# SiPM_Array_v3_2.net
KiCad netlist of a schematic drawn in Altium Designer
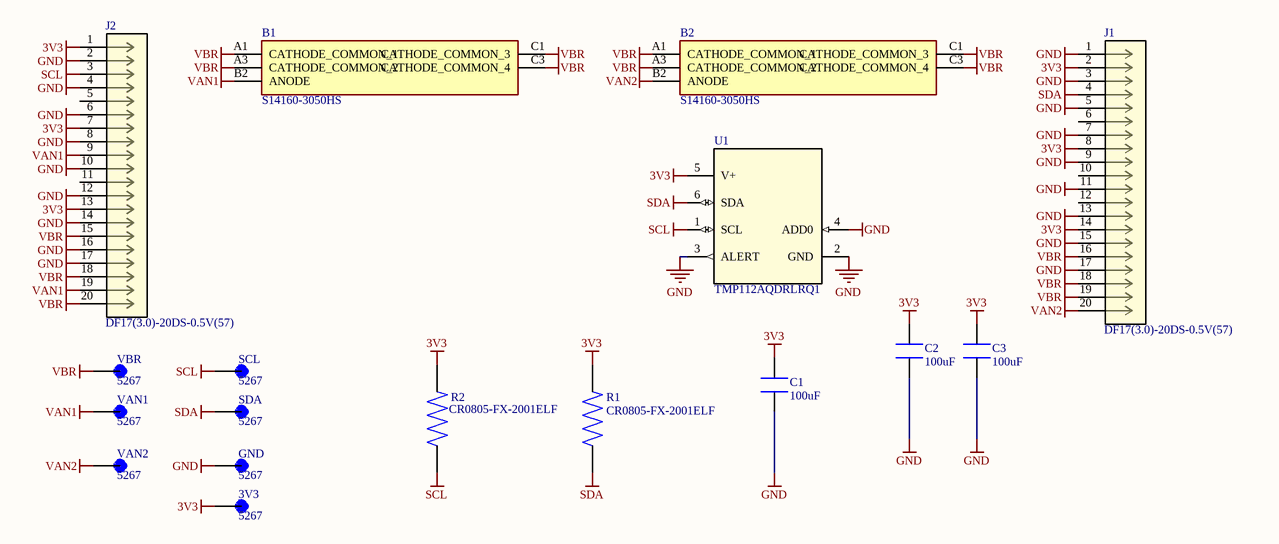
[diagram p0: SiPM_Array_v3.2.SchDoc]

(export (version "E")
  (design (tool "Eeschema 10.0.6"))
  (components
    (comp (ref "3V3")
      (value "5267")
      (footprint "KEYSTONE_5267")
      (description "TEST POINT (BLUE) - MINIATURE")
      (fields (field (name "MF") "Keystone Electronics"))
      (libsource (lib "5267") (part "5267"))
    )
    (comp (ref "B1")
      (value "S14160-3050HS")
      (footprint "S141603050HS")
      (libsource (lib "S14160-3050HS") (part "S14160-3050HS"))
    )
    (comp (ref "B2")
      (value "S14160-3050HS")
      (footprint "S141603050HS")
      (libsource (lib "S14160-3050HS") (part "S14160-3050HS"))
    )
    (comp (ref "C1")
      (value "100uF")
      (footprint "APSS Flight Parts:CAPACITOR_0805_2012M-70N")
      (fields
        (field (name "TOLERANCE") "±20%")
        (field (name "MF PART NO.") "GRM21BR60J107ME15L")
        (field (name "APSS STANDARD PART") "APSS Standard")
      )
      (libsource (lib "APSS Flight Parts") (part "GRM21BR60J107ME15L"))
    )
    (comp (ref "C2")
      (value "100uF")
      (footprint "APSS Flight Parts:CAPACITOR_0805_2012M-70N")
      (fields
        (field (name "TOLERANCE") "±20%")
        (field (name "MF PART NO.") "GRM21BR60J107ME15L")
        (field (name "APSS STANDARD PART") "APSS Standard")
      )
      (libsource (lib "APSS Flight Parts") (part "GRM21BR60J107ME15L"))
    )
    (comp (ref "C3")
      (value "100uF")
      (footprint "APSS Flight Parts:CAPACITOR_0805_2012M-70N")
      (fields
        (field (name "TOLERANCE") "±20%")
        (field (name "MF PART NO.") "GRM21BR60J107ME15L")
        (field (name "APSS STANDARD PART") "APSS Standard")
      )
      (libsource (lib "APSS Flight Parts") (part "GRM21BR60J107ME15L"))
    )
    (comp (ref "GND")
      (value "5267")
      (footprint "KEYSTONE_5267")
      (description "TEST POINT (BLUE) - MINIATURE")
      (fields (field (name "MF") "Keystone Electronics"))
      (libsource (lib "5267") (part "5267"))
    )
    (comp (ref "J1")
      (value "DF17(3.0)-20DS-0.5V(57)")
      (footprint "CONN_DF173.0-20DS-0.5V57_HIR")
      (description "Description")
      (fields (field (name "COPYRIGHT") "Copyright (C) 2025 Ultra Librarian. All rights reserved."))
      (libsource (lib "DF173P0-20DS-0P5V57") (part "DF173.0-20DS-0.5V57"))
    )
    (comp (ref "J2")
      (value "DF17(3.0)-20DS-0.5V(57)")
      (footprint "CONN_DF173.0-20DS-0.5V57_HIR")
      (description "Description")
      (fields (field (name "COPYRIGHT") "Copyright (C) 2025 Ultra Librarian. All rights reserved."))
      (libsource (lib "DF173P0-20DS-0P5V57") (part "DF173.0-20DS-0.5V57"))
    )
    (comp (ref "R1")
      (value "CR0805-FX-2001ELF")
      (footprint "RESC2012X60N")
      (description "Res 0805 2k 1% 125mW ¦ Bourns CR0805-FX-2001ELF")
      (fields (field (name "MF") "Bourns"))
      (libsource (lib "CR0805-FX-2001ELF") (part "CR0805-FX-2001ELF"))
    )
    (comp (ref "R2")
      (value "CR0805-FX-2001ELF")
      (footprint "RESC2012X60N")
      (description "Res 0805 2k 1% 125mW ¦ Bourns CR0805-FX-2001ELF")
      (fields (field (name "MF") "Bourns"))
      (libsource (lib "CR0805-FX-2001ELF") (part "CR0805-FX-2001ELF"))
    )
    (comp (ref "SCL")
      (value "5267")
      (footprint "KEYSTONE_5267")
      (description "TEST POINT (BLUE) - MINIATURE")
      (fields (field (name "MF") "Keystone Electronics"))
      (libsource (lib "5267") (part "5267"))
    )
    (comp (ref "SDA")
      (value "5267")
      (footprint "KEYSTONE_5267")
      (description "TEST POINT (BLUE) - MINIATURE")
      (fields (field (name "MF") "Keystone Electronics"))
      (libsource (lib "5267") (part "5267"))
    )
    (comp (ref "U1")
      (value "TMP112AQDRLRQ1")
      (footprint "DRL0006A")
      (description "No Description Available")
      (fields (field (name "MANUFACTURER") "Texas Instruments"))
      (libsource (lib "APSS3Rad") (part "TMP112AQDRLRQ1"))
    )
    (comp (ref "VAN1")
      (value "5267")
      (footprint "KEYSTONE_5267")
      (description "TEST POINT (BLUE) - MINIATURE")
      (fields (field (name "MF") "Keystone Electronics"))
      (libsource (lib "5267") (part "5267"))
    )
    (comp (ref "VAN2")
      (value "5267")
      (footprint "KEYSTONE_5267")
      (description "TEST POINT (BLUE) - MINIATURE")
      (fields (field (name "MF") "Keystone Electronics"))
      (libsource (lib "5267") (part "5267"))
    )
    (comp (ref "VBR")
      (value "5267")
      (footprint "KEYSTONE_5267")
      (description "TEST POINT (BLUE) - MINIATURE")
      (fields (field (name "MF") "Keystone Electronics"))
      (libsource (lib "5267") (part "5267"))
    )
  )
  (nets
    (net (code "1") (name "3V3") (class "Default")
      (node (ref "3V3") (pin "TP") (pinfunction "TP_TP") (pintype "passive"))
      (node (ref "C1") (pin "2") (pinfunction "2_2") (pintype "passive"))
      (node (ref "C2") (pin "2") (pinfunction "2_2") (pintype "passive"))
      (node (ref "C3") (pin "2") (pinfunction "2_2") (pintype "passive"))
      (node (ref "J1") (pin "14") (pinfunction "14_14") (pintype "passive"))
      (node (ref "J1") (pin "2") (pinfunction "2_2") (pintype "passive"))
      (node (ref "J1") (pin "8") (pinfunction "8_8") (pintype "passive"))
      (node (ref "J2") (pin "1") (pinfunction "1_1") (pintype "passive"))
      (node (ref "J2") (pin "13") (pinfunction "13_13") (pintype "passive"))
      (node (ref "J2") (pin "7") (pinfunction "7_7") (pintype "passive"))
      (node (ref "R1") (pin "1") (pinfunction "1_1") (pintype "passive"))
      (node (ref "R2") (pin "1") (pinfunction "1_1") (pintype "passive"))
      (node (ref "U1") (pin "5") (pinfunction "V+_5") (pintype "power_in"))
    )
    (net (code "2") (name "GND") (class "Default")
      (node (ref "C1") (pin "1") (pinfunction "1_1") (pintype "passive"))
      (node (ref "C2") (pin "1") (pinfunction "1_1") (pintype "passive"))
      (node (ref "C3") (pin "1") (pinfunction "1_1") (pintype "passive"))
      (node (ref "GND") (pin "TP") (pinfunction "TP_TP") (pintype "passive"))
      (node (ref "J1") (pin "1") (pinfunction "1_1") (pintype "passive"))
      (node (ref "J1") (pin "11") (pinfunction "11_11") (pintype "passive"))
      (node (ref "J1") (pin "13") (pinfunction "13_13") (pintype "passive"))
      (node (ref "J1") (pin "15") (pinfunction "15_15") (pintype "passive"))
      (node (ref "J1") (pin "17") (pinfunction "17_17") (pintype "passive"))
      (node (ref "J1") (pin "3") (pinfunction "3_3") (pintype "passive"))
      (node (ref "J1") (pin "5") (pinfunction "5_5") (pintype "passive"))
      (node (ref "J1") (pin "7") (pinfunction "7_7") (pintype "passive"))
      (node (ref "J1") (pin "9") (pinfunction "9_9") (pintype "passive"))
      (node (ref "J2") (pin "10") (pinfunction "10_10") (pintype "passive"))
      (node (ref "J2") (pin "12") (pinfunction "12_12") (pintype "passive"))
      (node (ref "J2") (pin "14") (pinfunction "14_14") (pintype "passive"))
      (node (ref "J2") (pin "16") (pinfunction "16_16") (pintype "passive"))
      (node (ref "J2") (pin "17") (pinfunction "17_17") (pintype "passive"))
      (node (ref "J2") (pin "2") (pinfunction "2_2") (pintype "passive"))
      (node (ref "J2") (pin "4") (pinfunction "4_4") (pintype "passive"))
      (node (ref "J2") (pin "6") (pinfunction "6_6") (pintype "passive"))
      (node (ref "J2") (pin "8") (pinfunction "8_8") (pintype "passive"))
      (node (ref "U1") (pin "2") (pinfunction "GND_2") (pintype "power_in"))
      (node (ref "U1") (pin "3") (pinfunction "ALERT_3") (pintype "output"))
      (node (ref "U1") (pin "4") (pinfunction "ADD0_4") (pintype "input"))
    )
    (net (code "3") (name "SCL") (class "Default")
      (node (ref "J2") (pin "3") (pinfunction "3_3") (pintype "passive"))
      (node (ref "R2") (pin "2") (pinfunction "2_2") (pintype "passive"))
      (node (ref "SCL") (pin "TP") (pinfunction "TP_TP") (pintype "passive"))
      (node (ref "U1") (pin "1") (pinfunction "SCL_1") (pintype "bidirectional"))
    )
    (net (code "4") (name "SDA") (class "Default")
      (node (ref "J1") (pin "4") (pinfunction "4_4") (pintype "passive"))
      (node (ref "R1") (pin "2") (pinfunction "2_2") (pintype "passive"))
      (node (ref "SDA") (pin "TP") (pinfunction "TP_TP") (pintype "passive"))
      (node (ref "U1") (pin "6") (pinfunction "SDA_6") (pintype "bidirectional"))
    )
    (net (code "5") (name "VAN1") (class "Default")
      (node (ref "B1") (pin "B2") (pinfunction "ANODE_B2") (pintype "passive"))
      (node (ref "J2") (pin "19") (pinfunction "19_19") (pintype "passive"))
      (node (ref "J2") (pin "9") (pinfunction "9_9") (pintype "passive"))
      (node (ref "VAN1") (pin "TP") (pinfunction "TP_TP") (pintype "passive"))
    )
    (net (code "6") (name "VAN2") (class "Default")
      (node (ref "B2") (pin "B2") (pinfunction "ANODE_B2") (pintype "passive"))
      (node (ref "J1") (pin "20") (pinfunction "20_20") (pintype "passive"))
      (node (ref "VAN2") (pin "TP") (pinfunction "TP_TP") (pintype "passive"))
    )
    (net (code "7") (name "VBR") (class "Default")
      (node (ref "B1") (pin "A1") (pinfunction "CATHODE_COMMON_1_A1") (pintype "passive"))
      (node (ref "B1") (pin "A3") (pinfunction "CATHODE_COMMON_2_A3") (pintype "passive"))
      (node (ref "B1") (pin "C1") (pinfunction "CATHODE_COMMON_3_C1") (pintype "passive"))
      (node (ref "B1") (pin "C3") (pinfunction "CATHODE_COMMON_4_C3") (pintype "passive"))
      (node (ref "B2") (pin "A1") (pinfunction "CATHODE_COMMON_1_A1") (pintype "passive"))
      (node (ref "B2") (pin "A3") (pinfunction "CATHODE_COMMON_2_A3") (pintype "passive"))
      (node (ref "B2") (pin "C1") (pinfunction "CATHODE_COMMON_3_C1") (pintype "passive"))
      (node (ref "B2") (pin "C3") (pinfunction "CATHODE_COMMON_4_C3") (pintype "passive"))
      (node (ref "J1") (pin "16") (pinfunction "16_16") (pintype "passive"))
      (node (ref "J1") (pin "18") (pinfunction "18_18") (pintype "passive"))
      (node (ref "J1") (pin "19") (pinfunction "19_19") (pintype "passive"))
      (node (ref "J2") (pin "15") (pinfunction "15_15") (pintype "passive"))
      (node (ref "J2") (pin "18") (pinfunction "18_18") (pintype "passive"))
      (node (ref "J2") (pin "20") (pinfunction "20_20") (pintype "passive"))
      (node (ref "VBR") (pin "TP") (pinfunction "TP_TP") (pintype "passive"))
    )
    (net (code "8") (name "unconnected-(J1-Pad6)") (class "Default")
      (node (ref "J1") (pin "6") (pinfunction "6_6") (pintype "passive"))
    )
    (net (code "9") (name "unconnected-(J1-Pad10)") (class "Default")
      (node (ref "J1") (pin "10") (pinfunction "10_10") (pintype "passive"))
    )
    (net (code "10") (name "unconnected-(J1-Pad12)") (class "Default")
      (node (ref "J1") (pin "12") (pinfunction "12_12") (pintype "passive"))
    )
    (net (code "11") (name "unconnected-(J2-Pad5)") (class "Default")
      (node (ref "J2") (pin "5") (pinfunction "5_5") (pintype "passive"))
    )
    (net (code "12") (name "unconnected-(J2-Pad11)") (class "Default")
      (node (ref "J2") (pin "11") (pinfunction "11_11") (pintype "passive"))
    )
  )
)
